# GB202-CC-from-SF-Base.net
KiCad netlist of a schematic drawn in EAGLE
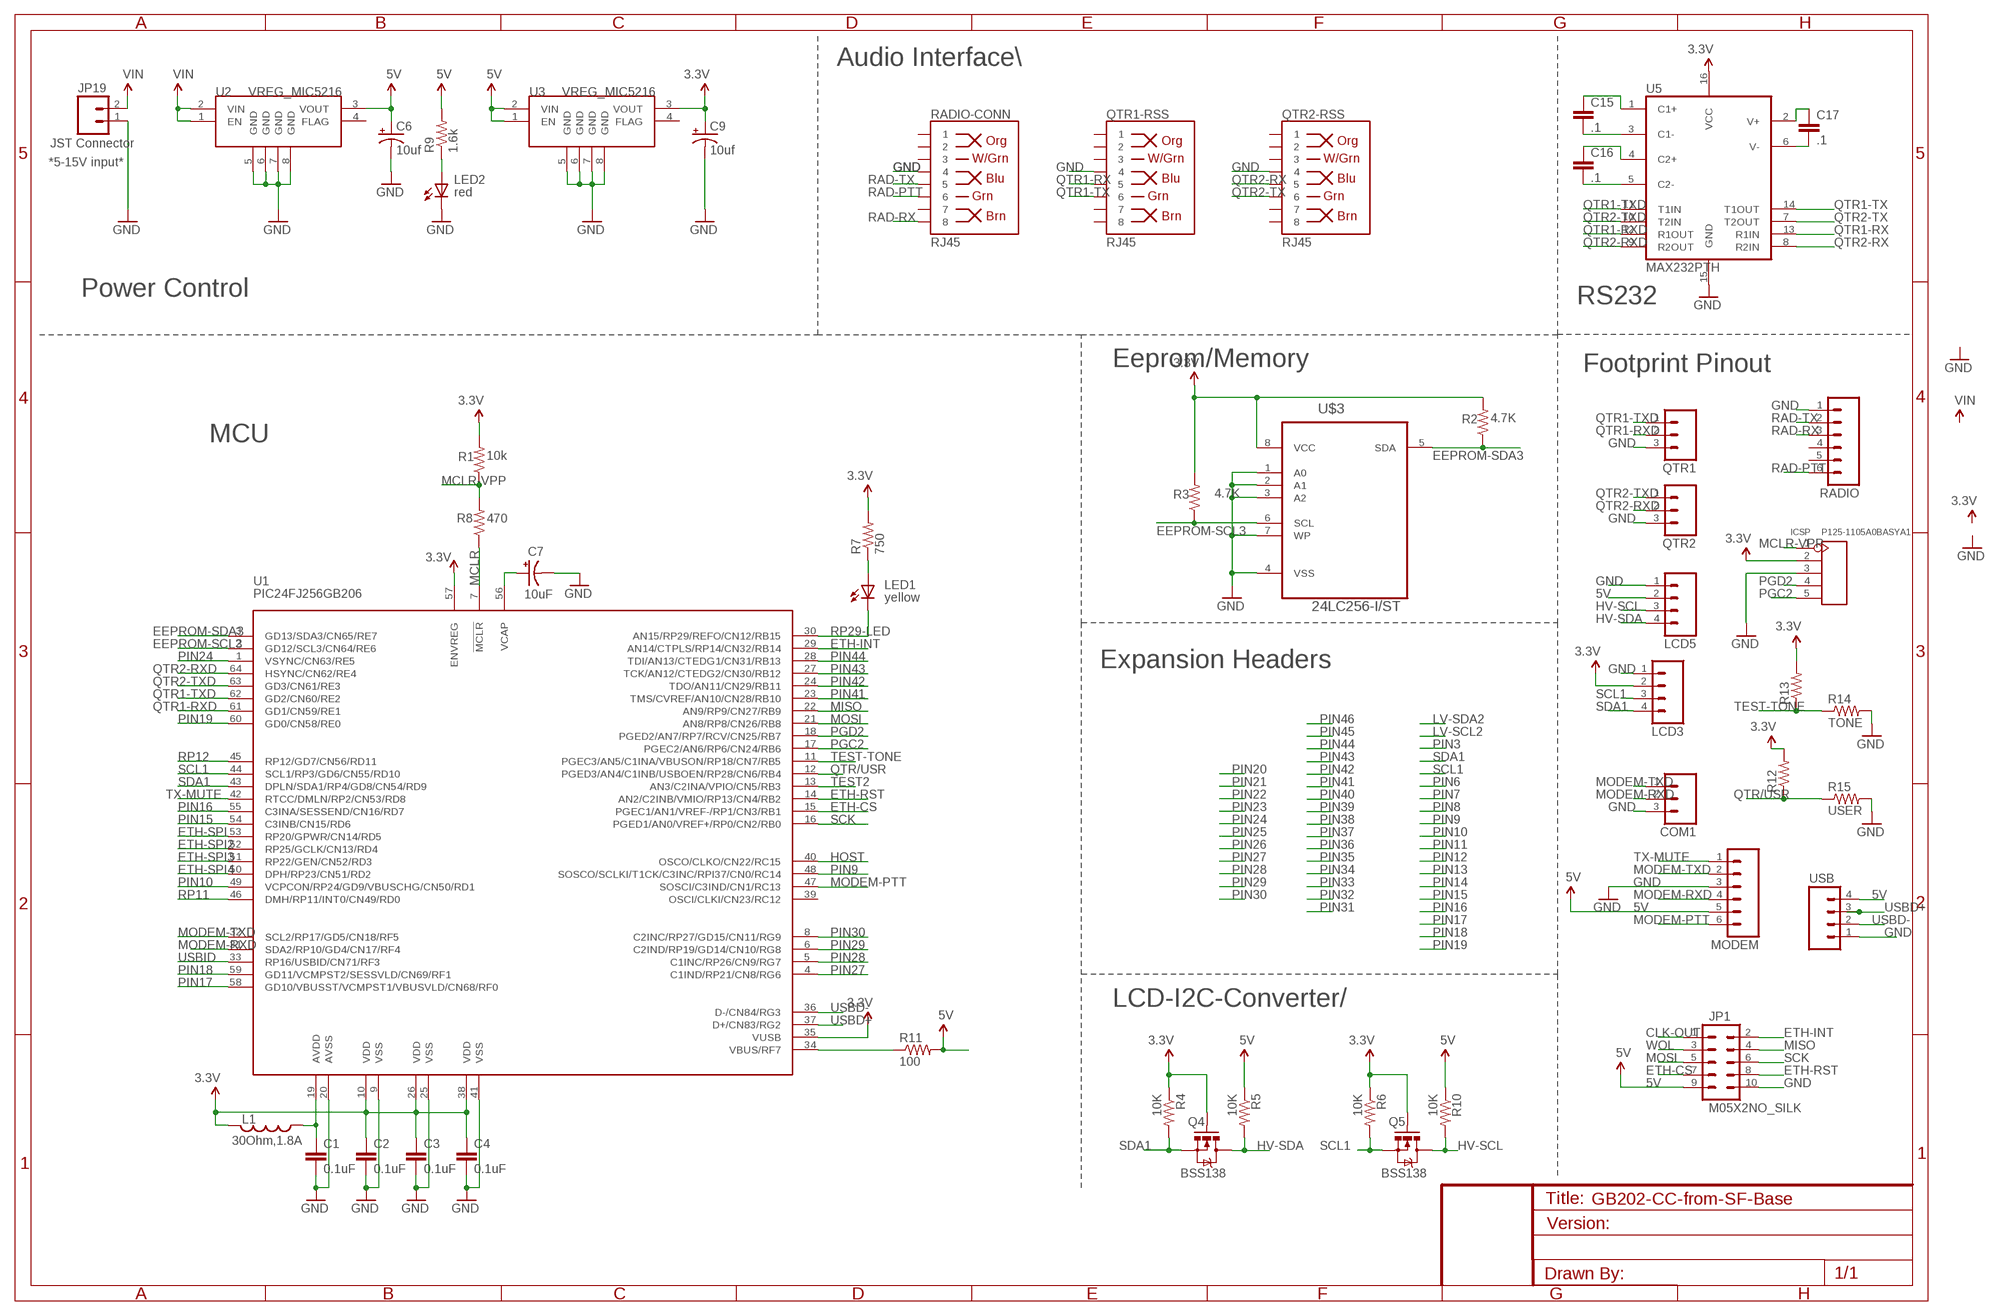
[diagram p0: schematic, sheet 1]

(export (version "E")
  (design (tool "Eeschema 10.0.6"))
  (components
    (comp (ref "C1")
      (value "0.1uF")
      (footprint "eagle-import:0402-CAP")
      (libsource (lib "eagle-import") (part "CAP0402-CAP"))
    )
    (comp (ref "C2")
      (value "0.1uF")
      (footprint "eagle-import:0402-CAP")
      (libsource (lib "eagle-import") (part "CAP0402-CAP"))
    )
    (comp (ref "C3")
      (value "0.1uF")
      (footprint "eagle-import:0402-CAP")
      (libsource (lib "eagle-import") (part "CAP0402-CAP"))
    )
    (comp (ref "C4")
      (value "0.1uF")
      (footprint "eagle-import:0402-CAP")
      (libsource (lib "eagle-import") (part "CAP0402-CAP"))
    )
    (comp (ref "C6")
      (value "10uf")
      (footprint "eagle-import:EIA3216")
      (libsource (lib "eagle-import") (part "SparkFun-Capacitors_CAP_POL1206"))
    )
    (comp (ref "C7")
      (value "10uF")
      (footprint "eagle-import:EIA3216")
      (libsource (lib "eagle-import") (part "CAP_POL1206"))
    )
    (comp (ref "C9")
      (value "10uf")
      (footprint "eagle-import:EIA3216")
      (libsource (lib "eagle-import") (part "SparkFun-Capacitors_CAP_POL1206"))
    )
    (comp (ref "C15")
      (value ".1")
      (footprint "eagle-import:CAP-PTH-SMALL")
      (libsource (lib "eagle-import") (part "CAPPTH"))
    )
    (comp (ref "C16")
      (value ".1")
      (footprint "eagle-import:CAP-PTH-SMALL")
      (libsource (lib "eagle-import") (part "CAPPTH"))
    )
    (comp (ref "C17")
      (value ".1")
      (footprint "eagle-import:CAP-PTH-SMALL")
      (libsource (lib "eagle-import") (part "CAPPTH"))
    )
    (comp (ref "COM1")
      (value "M031X03_NO_SILK")
      (footprint "eagle-import:1X03_NO_SILK")
      (libsource (lib "eagle-import") (part "M031X03_NO_SILK"))
    )
    (comp (ref "ICSP")
      (value "P125-1105A0BASYA1")
      (footprint "eagle-import:H5-2.54")
      (libsource (lib "eagle-import") (part "DIP-BLACK-MALE-HEADER(5P-2.54)"))
    )
    (comp (ref "JP1")
      (value "M05X2NO_SILK")
      (footprint "eagle-import:2X5_NOSILK")
      (libsource (lib "eagle-import") (part "M05X2NO_SILK"))
    )
    (comp (ref "JP19")
      (value "JST Connector")
      (footprint "eagle-import:JST-2-SMD")
      (libsource (lib "eagle-import") (part "M02-JST-2MM-SMT"))
    )
    (comp (ref "L1")
      (value "30Ohm,1.8A")
      (footprint "eagle-import:0603")
      (libsource (lib "eagle-import") (part "INDUCTOR0603"))
    )
    (comp (ref "LCD3")
      (value "M04LONGPADS")
      (footprint "eagle-import:1X04_LONGPADS")
      (libsource (lib "eagle-import") (part "M04LONGPADS"))
    )
    (comp (ref "LCD5")
      (value "M04LONGPADS")
      (footprint "eagle-import:1X04_LONGPADS")
      (libsource (lib "eagle-import") (part "M04LONGPADS"))
    )
    (comp (ref "LED1")
      (value "LY L29K-J1K2-26-Z")
      (footprint "eagle-import:LED-0603")
      (libsource (lib "eagle-import") (part "SparkFun-LED_LED0603"))
    )
    (comp (ref "LED2")
      (value "LS L29K-G1J2-1-Z")
      (footprint "eagle-import:LED-0603")
      (libsource (lib "eagle-import") (part "LED0603"))
    )
    (comp (ref "MODEM")
      (value "M06LONGPADS")
      (footprint "eagle-import:1X06_LONGPADS")
      (libsource (lib "eagle-import") (part "M06LONGPADS"))
    )
    (comp (ref "Q4")
      (value "BSS138")
      (footprint "eagle-import:SOT23-3")
      (libsource (lib "eagle-import") (part "MOSFET-NCHANNELSMD"))
    )
    (comp (ref "Q5")
      (value "BSS138")
      (footprint "eagle-import:SOT23-3")
      (libsource (lib "eagle-import") (part "MOSFET-NCHANNELSMD"))
    )
    (comp (ref "QTR1")
      (value "M031X03_NO_SILK")
      (footprint "eagle-import:1X03_NO_SILK")
      (libsource (lib "eagle-import") (part "M031X03_NO_SILK"))
    )
    (comp (ref "QTR1-RSS")
      (value "RJ45")
      (footprint "eagle-import:RJ45-8")
      (libsource (lib "eagle-import") (part "RJ45-8PTH"))
    )
    (comp (ref "QTR2")
      (value "M031X03_NO_SILK")
      (footprint "eagle-import:1X03_NO_SILK")
      (libsource (lib "eagle-import") (part "M031X03_NO_SILK"))
    )
    (comp (ref "QTR2-RSS")
      (value "RJ45")
      (footprint "eagle-import:RJ45-8")
      (libsource (lib "eagle-import") (part "RJ45-8PTH"))
    )
    (comp (ref "R1")
      (value "10k")
      (footprint "eagle-import:R0402")
      (libsource (lib "eagle-import") (part "R-US_R0402"))
    )
    (comp (ref "R2")
      (value "4.7K")
      (footprint "eagle-import:R0402")
      (libsource (lib "eagle-import") (part "R-US_R0402"))
    )
    (comp (ref "R3")
      (value "4.7K")
      (footprint "eagle-import:R0402")
      (libsource (lib "eagle-import") (part "R-US_R0402"))
    )
    (comp (ref "R4")
      (value "10K")
      (footprint "eagle-import:0402-RES")
      (libsource (lib "eagle-import") (part "RESISTOR0402-RES"))
    )
    (comp (ref "R5")
      (value "10K")
      (footprint "eagle-import:0603-RES")
      (libsource (lib "eagle-import") (part "RESISTOR0603-RES"))
    )
    (comp (ref "R6")
      (value "10K")
      (footprint "eagle-import:0402-RES")
      (libsource (lib "eagle-import") (part "RESISTOR0402-RES"))
    )
    (comp (ref "R7")
      (value "750")
      (footprint "eagle-import:0603-RES")
      (libsource (lib "eagle-import") (part "SparkFun-Resistors_RESISTOR0603-RES"))
    )
    (comp (ref "R8")
      (value "470")
      (footprint "eagle-import:R0402")
      (libsource (lib "eagle-import") (part "R-US_R0402"))
    )
    (comp (ref "R9")
      (value "1.6k")
      (footprint "eagle-import:0603-RES")
      (libsource (lib "eagle-import") (part "SparkFun-Resistors_RESISTOR0603-RES"))
    )
    (comp (ref "R10")
      (value "10K")
      (footprint "eagle-import:0603-RES")
      (libsource (lib "eagle-import") (part "RESISTOR0603-RES"))
    )
    (comp (ref "R11")
      (value "100")
      (footprint "eagle-import:0402-RES")
      (libsource (lib "eagle-import") (part "RESISTOR0402-RES"))
    )
    (comp (ref "R12")
      (value "R-US_R0402")
      (footprint "eagle-import:R0402")
      (libsource (lib "eagle-import") (part "R-US_R0402"))
    )
    (comp (ref "R13")
      (value "R-US_R0402")
      (footprint "eagle-import:R0402")
      (libsource (lib "eagle-import") (part "R-US_R0402"))
    )
    (comp (ref "R14")
      (value "TONE")
      (footprint "eagle-import:R1206")
      (libsource (lib "eagle-import") (part "R-US_R1206"))
    )
    (comp (ref "R15")
      (value "USER")
      (footprint "eagle-import:R1206")
      (libsource (lib "eagle-import") (part "R-US_R1206"))
    )
    (comp (ref "RADIO")
      (value "M06LONGPADS")
      (footprint "eagle-import:1X06_LONGPADS")
      (libsource (lib "eagle-import") (part "M06LONGPADS"))
    )
    (comp (ref "RADIO-CONN")
      (value "RJ45")
      (footprint "eagle-import:RJ45-8")
      (libsource (lib "eagle-import") (part "RJ45-8PTH"))
    )
    (comp (ref "U$3")
      (value "24LC256-I/ST")
      (footprint "eagle-import:SOP65P638X110-8N")
      (libsource (lib "eagle-import") (part "24LC256-I/ST"))
    )
    (comp (ref "U1")
      (value "PIC24FJ256GB206")
      (footprint "eagle-import:PIC24FXXX_TQFP64")
      (libsource (lib "eagle-import") (part "PIC24FXXXDAX06"))
    )
    (comp (ref "U2")
      (value "VREG_MIC5216")
      (footprint "eagle-import:MSOP8")
      (libsource (lib "eagle-import") (part "VREG_MIC5216"))
    )
    (comp (ref "U3")
      (value "VREG_MIC5216")
      (footprint "eagle-import:MSOP8")
      (libsource (lib "eagle-import") (part "VREG_MIC5216"))
    )
    (comp (ref "U5")
      (value "MAX232PTH")
      (footprint "eagle-import:DIL16")
      (libsource (lib "eagle-import") (part "MAX232PTH"))
    )
    (comp (ref "USB")
      (value "M04PTH")
      (footprint "eagle-import:1X04")
      (libsource (lib "eagle-import") (part "M04PTH"))
    )
  )
  (nets
    (net (code "1") (name "/CLK-OUT") (class "Default")
      (node (ref "JP1") (pin "1") (pinfunction "1_1") (pintype "passive"))
    )
    (net (code "2") (name "/EEPROM-SCL3") (class "Default")
      (node (ref "R3") (pin "1") (pinfunction "1_1") (pintype "passive"))
      (node (ref "U$3") (pin "6") (pinfunction "SCL_6") (pintype "input"))
      (node (ref "U1") (pin "2") (pinfunction "GD12/SCL3/CN64/RE6_2") (pintype "bidirectional"))
    )
    (net (code "3") (name "/EEPROM-SDA3") (class "Default")
      (node (ref "R2") (pin "1") (pinfunction "1_1") (pintype "passive"))
      (node (ref "U$3") (pin "5") (pinfunction "SDA_5") (pintype "bidirectional"))
      (node (ref "U1") (pin "3") (pinfunction "GD13/SDA3/CN65/RE7_3") (pintype "bidirectional"))
    )
    (net (code "4") (name "/ETH-CS") (class "Default")
      (node (ref "JP1") (pin "7") (pinfunction "7_7") (pintype "passive"))
      (node (ref "U1") (pin "15") (pinfunction "PGEC1/AN1/VREF-/RP1/CN3/RB1_15") (pintype "bidirectional"))
    )
    (net (code "5") (name "/ETH-INT") (class "Default")
      (node (ref "JP1") (pin "2") (pinfunction "2_2") (pintype "passive"))
      (node (ref "U1") (pin "29") (pinfunction "AN14/CTPLS/RP14/CN32/RB14_29") (pintype "bidirectional"))
    )
    (net (code "6") (name "/ETH-RST") (class "Default")
      (node (ref "JP1") (pin "8") (pinfunction "8_8") (pintype "passive"))
      (node (ref "U1") (pin "14") (pinfunction "AN2/C2INB/VMIO/RP13/CN4/RB2_14") (pintype "bidirectional"))
    )
    (net (code "7") (name "/ETH-SPI") (class "Default")
      (node (ref "U1") (pin "53") (pinfunction "RP20/GPWR/CN14/RD5_53") (pintype "bidirectional"))
    )
    (net (code "8") (name "/ETH-SPI2") (class "Default")
      (node (ref "U1") (pin "52") (pinfunction "RP25/GCLK/CN13/RD4_52") (pintype "bidirectional"))
    )
    (net (code "9") (name "/ETH-SPI3") (class "Default")
      (node (ref "U1") (pin "51") (pinfunction "RP22/GEN/CN52/RD3_51") (pintype "bidirectional"))
    )
    (net (code "10") (name "/ETH-SPI4") (class "Default")
      (node (ref "U1") (pin "50") (pinfunction "DPH/RP23/CN51/RD2_50") (pintype "bidirectional"))
    )
    (net (code "11") (name "/HOST") (class "Default")
      (node (ref "U1") (pin "40") (pinfunction "OSCO/CLKO/CN22/RC15_40") (pintype "bidirectional"))
    )
    (net (code "12") (name "/HV-SCL") (class "Default")
      (node (ref "LCD5") (pin "3") (pinfunction "3_3") (pintype "passive"))
      (node (ref "Q5") (pin "3") (pinfunction "D_3") (pintype "passive"))
      (node (ref "R10") (pin "2") (pinfunction "2_2") (pintype "passive"))
    )
    (net (code "13") (name "/HV-SDA") (class "Default")
      (node (ref "LCD5") (pin "4") (pinfunction "4_4") (pintype "passive"))
      (node (ref "Q4") (pin "3") (pinfunction "D_3") (pintype "passive"))
      (node (ref "R5") (pin "2") (pinfunction "2_2") (pintype "passive"))
    )
    (net (code "16") (name "/MCLR") (class "Default")
      (node (ref "R8") (pin "1") (pinfunction "1_1") (pintype "passive"))
      (node (ref "U1") (pin "7") (pinfunction "~{MCLR}_7") (pintype "input"))
    )
    (net (code "17") (name "/MCLR-VPP") (class "Default")
      (node (ref "ICSP") (pin "1") (pinfunction "1_1") (pintype "bidirectional"))
      (node (ref "R1") (pin "1") (pinfunction "1_1") (pintype "passive"))
      (node (ref "R8") (pin "2") (pinfunction "2_2") (pintype "passive"))
    )
    (net (code "18") (name "/MISO") (class "Default")
      (node (ref "JP1") (pin "4") (pinfunction "4_4") (pintype "passive"))
      (node (ref "U1") (pin "22") (pinfunction "AN9/RP9/CN27/RB9_22") (pintype "bidirectional"))
    )
    (net (code "19") (name "/MODEM-PTT") (class "Default")
      (node (ref "MODEM") (pin "6") (pinfunction "6_6") (pintype "passive"))
      (node (ref "U1") (pin "47") (pinfunction "SOSCI/C3IND/CN1/RC13_47") (pintype "bidirectional"))
    )
    (net (code "20") (name "/MODEM-RXD") (class "Default")
      (node (ref "COM1") (pin "2") (pinfunction "2_2") (pintype "passive"))
      (node (ref "MODEM") (pin "4") (pinfunction "4_4") (pintype "passive"))
      (node (ref "U1") (pin "31") (pinfunction "SDA2/RP10/GD4/CN17/RF4_31") (pintype "bidirectional"))
    )
    (net (code "21") (name "/MODEM-TXD") (class "Default")
      (node (ref "COM1") (pin "1") (pinfunction "1_1") (pintype "passive"))
      (node (ref "MODEM") (pin "2") (pinfunction "2_2") (pintype "passive"))
      (node (ref "U1") (pin "32") (pinfunction "SCL2/RP17/GD5/CN18/RF5_32") (pintype "bidirectional"))
    )
    (net (code "22") (name "/MOSI") (class "Default")
      (node (ref "JP1") (pin "5") (pinfunction "5_5") (pintype "passive"))
      (node (ref "U1") (pin "21") (pinfunction "AN8/RP8/CN26/RB8_21") (pintype "bidirectional"))
    )
    (net (code "23") (name "/PGC2") (class "Default")
      (node (ref "ICSP") (pin "5") (pinfunction "5_5") (pintype "bidirectional"))
      (node (ref "U1") (pin "17") (pinfunction "PGEC2/AN6/RP6/CN24/RB6_17") (pintype "bidirectional"))
    )
    (net (code "24") (name "/PGD2") (class "Default")
      (node (ref "ICSP") (pin "4") (pinfunction "4_4") (pintype "bidirectional"))
      (node (ref "U1") (pin "18") (pinfunction "PGED2/AN7/RP7/RCV/CN25/RB7_18") (pintype "bidirectional"))
    )
    (net (code "29") (name "/PIN9") (class "Default")
      (node (ref "U1") (pin "48") (pinfunction "SOSCO/SCLKI/T1CK/C3INC/RPI37/CN0/RC14_48") (pintype "bidirectional"))
    )
    (net (code "30") (name "/PIN10") (class "Default")
      (node (ref "U1") (pin "49") (pinfunction "VCPCON/RP24/GD9/VBUSCHG/CN50/RD1_49") (pintype "bidirectional"))
    )
    (net (code "35") (name "/PIN15") (class "Default")
      (node (ref "U1") (pin "54") (pinfunction "C3INB/CN15/RD6_54") (pintype "bidirectional"))
    )
    (net (code "36") (name "/PIN16") (class "Default")
      (node (ref "U1") (pin "55") (pinfunction "C3INA/SESSEND/CN16/RD7_55") (pintype "bidirectional"))
    )
    (net (code "37") (name "/PIN17") (class "Default")
      (node (ref "U1") (pin "58") (pinfunction "GD10/VBUSST/VCMPST1/VBUSVLD/CN68/RF0_58") (pintype "bidirectional"))
    )
    (net (code "38") (name "/PIN18") (class "Default")
      (node (ref "U1") (pin "59") (pinfunction "GD11/VCMPST2/SESSVLD/CN69/RF1_59") (pintype "bidirectional"))
    )
    (net (code "39") (name "/PIN19") (class "Default")
      (node (ref "U1") (pin "60") (pinfunction "GD0/CN58/RE0_60") (pintype "bidirectional"))
    )
    (net (code "44") (name "/PIN24") (class "Default")
      (node (ref "U1") (pin "1") (pinfunction "VSYNC/CN63/RE5_1") (pintype "bidirectional"))
    )
    (net (code "47") (name "/PIN27") (class "Default")
      (node (ref "U1") (pin "4") (pinfunction "C1IND/RP21/CN8/RG6_4") (pintype "bidirectional"))
    )
    (net (code "48") (name "/PIN28") (class "Default")
      (node (ref "U1") (pin "5") (pinfunction "C1INC/RP26/CN9/RG7_5") (pintype "bidirectional"))
    )
    (net (code "49") (name "/PIN29") (class "Default")
      (node (ref "U1") (pin "6") (pinfunction "C2IND/RP19/GD14/CN10/RG8_6") (pintype "bidirectional"))
    )
    (net (code "50") (name "/PIN30") (class "Default")
      (node (ref "U1") (pin "8") (pinfunction "C2INC/RP27/GD15/CN11/RG9_8") (pintype "bidirectional"))
    )
    (net (code "61") (name "/PIN41") (class "Default")
      (node (ref "U1") (pin "23") (pinfunction "TMS/CVREF/AN10/CN28/RB10_23") (pintype "bidirectional"))
    )
    (net (code "62") (name "/PIN42") (class "Default")
      (node (ref "U1") (pin "24") (pinfunction "TDO/AN11/CN29/RB11_24") (pintype "bidirectional"))
    )
    (net (code "63") (name "/PIN43") (class "Default")
      (node (ref "U1") (pin "27") (pinfunction "TCK/AN12/CTEDG2/CN30/RB12_27") (pintype "bidirectional"))
    )
    (net (code "64") (name "/PIN44") (class "Default")
      (node (ref "U1") (pin "28") (pinfunction "TDI/AN13/CTEDG1/CN31/RB13_28") (pintype "bidirectional"))
    )
    (net (code "67") (name "/QTR1-RX") (class "Default")
      (node (ref "QTR1-RSS") (pin "5") (pinfunction "5_5") (pintype "bidirectional"))
      (node (ref "U5") (pin "13") (pinfunction "R1IN_13") (pintype "input"))
    )
    (net (code "68") (name "/QTR1-RXD") (class "Default")
      (node (ref "QTR1") (pin "2") (pinfunction "2_2") (pintype "passive"))
      (node (ref "U1") (pin "61") (pinfunction "GD1/CN59/RE1_61") (pintype "bidirectional"))
      (node (ref "U5") (pin "12") (pinfunction "R1OUT_12") (pintype "output"))
    )
    (net (code "69") (name "/QTR1-TX") (class "Default")
      (node (ref "QTR1-RSS") (pin "6") (pinfunction "6_6") (pintype "bidirectional"))
      (node (ref "U5") (pin "14") (pinfunction "T1OUT_14") (pintype "output"))
    )
    (net (code "70") (name "/QTR1-TXD") (class "Default")
      (node (ref "QTR1") (pin "1") (pinfunction "1_1") (pintype "passive"))
      (node (ref "U1") (pin "62") (pinfunction "GD2/CN60/RE2_62") (pintype "bidirectional"))
      (node (ref "U5") (pin "11") (pinfunction "T1IN_11") (pintype "input"))
    )
    (net (code "71") (name "/QTR2-RX") (class "Default")
      (node (ref "QTR2-RSS") (pin "5") (pinfunction "5_5") (pintype "bidirectional"))
      (node (ref "U5") (pin "8") (pinfunction "R2IN_8") (pintype "input"))
    )
    (net (code "72") (name "/QTR2-RXD") (class "Default")
      (node (ref "QTR2") (pin "2") (pinfunction "2_2") (pintype "passive"))
      (node (ref "U1") (pin "64") (pinfunction "HSYNC/CN62/RE4_64") (pintype "bidirectional"))
      (node (ref "U5") (pin "9") (pinfunction "R2OUT_9") (pintype "output"))
    )
    (net (code "73") (name "/QTR2-TX") (class "Default")
      (node (ref "QTR2-RSS") (pin "6") (pinfunction "6_6") (pintype "bidirectional"))
      (node (ref "U5") (pin "7") (pinfunction "T2OUT_7") (pintype "output"))
    )
    (net (code "74") (name "/QTR2-TXD") (class "Default")
      (node (ref "QTR2") (pin "1") (pinfunction "1_1") (pintype "passive"))
      (node (ref "U1") (pin "63") (pinfunction "GD3/CN61/RE3_63") (pintype "bidirectional"))
      (node (ref "U5") (pin "10") (pinfunction "T2IN_10") (pintype "input"))
    )
    (net (code "75") (name "/QTR{slash}USR") (class "Default")
      (node (ref "R12") (pin "1") (pinfunction "1_1") (pintype "passive"))
      (node (ref "R15") (pin "1") (pinfunction "1_1") (pintype "passive"))
      (node (ref "U1") (pin "12") (pinfunction "PGED3/AN4/C1INB/USBOEN/RP28/CN6/RB4_12") (pintype "bidirectional"))
    )
    (net (code "76") (name "/RAD-PTT") (class "Default")
      (node (ref "RADIO") (pin "6") (pinfunction "6_6") (pintype "passive"))
      (node (ref "RADIO-CONN") (pin "6") (pinfunction "6_6") (pintype "bidirectional"))
    )
    (net (code "77") (name "/RAD-RX") (class "Default")
      (node (ref "RADIO") (pin "3") (pinfunction "3_3") (pintype "passive"))
      (node (ref "RADIO-CONN") (pin "8") (pinfunction "8_8") (pintype "bidirectional"))
    )
    (net (code "78") (name "/RAD-TX") (class "Default")
      (node (ref "RADIO") (pin "2") (pinfunction "2_2") (pintype "passive"))
      (node (ref "RADIO-CONN") (pin "5") (pinfunction "5_5") (pintype "bidirectional"))
    )
    (net (code "79") (name "/RP11") (class "Default")
      (node (ref "U1") (pin "46") (pinfunction "DMH/RP11/INT0/CN49/RD0_46") (pintype "bidirectional"))
    )
    (net (code "80") (name "/RP12") (class "Default")
      (node (ref "U1") (pin "45") (pinfunction "RP12/GD7/CN56/RD11_45") (pintype "bidirectional"))
    )
    (net (code "81") (name "/RP29-LED") (class "Default")
      (node (ref "LED1") (pin "C") (pinfunction "C_C") (pintype "passive"))
      (node (ref "U1") (pin "30") (pinfunction "AN15/RP29/REFO/CN12/RB15_30") (pintype "bidirectional"))
    )
    (net (code "82") (name "/SCK") (class "Default")
      (node (ref "JP1") (pin "6") (pinfunction "6_6") (pintype "passive"))
      (node (ref "U1") (pin "16") (pinfunction "PGED1/AN0/VREF+/RP0/CN2/RB0_16") (pintype "bidirectional"))
    )
    (net (code "83") (name "/SCL1") (class "Default")
      (node (ref "LCD3") (pin "3") (pinfunction "3_3") (pintype "passive"))
      (node (ref "Q5") (pin "2") (pinfunction "S_2") (pintype "passive"))
      (node (ref "R6") (pin "2") (pinfunction "2_2") (pintype "passive"))
      (node (ref "U1") (pin "44") (pinfunction "SCL1/RP3/GD6/CN55/RD10_44") (pintype "bidirectional"))
    )
    (net (code "84") (name "/SDA1") (class "Default")
      (node (ref "LCD3") (pin "4") (pinfunction "4_4") (pintype "passive"))
      (node (ref "Q4") (pin "2") (pinfunction "S_2") (pintype "passive"))
      (node (ref "R4") (pin "2") (pinfunction "2_2") (pintype "passive"))
      (node (ref "U1") (pin "43") (pinfunction "DPLN/SDA1/RP4/GD8/CN54/RD9_43") (pintype "bidirectional"))
    )
    (net (code "85") (name "/TEST-TONE") (class "Default")
      (node (ref "R13") (pin "1") (pinfunction "1_1") (pintype "passive"))
      (node (ref "R14") (pin "1") (pinfunction "1_1") (pintype "passive"))
      (node (ref "U1") (pin "11") (pinfunction "PGEC3/AN5/C1INA/VBUSON/RP18/CN7/RB5_11") (pintype "bidirectional"))
    )
    (net (code "86") (name "/TEST2") (class "Default")
      (node (ref "U1") (pin "13") (pinfunction "AN3/C2INA/VPIO/CN5/RB3_13") (pintype "bidirectional"))
    )
    (net (code "87") (name "/TX-MUTE") (class "Default")
      (node (ref "MODEM") (pin "1") (pinfunction "1_1") (pintype "passive"))
      (node (ref "U1") (pin "42") (pinfunction "RTCC/DMLN/RP2/CN53/RD8_42") (pintype "bidirectional"))
    )
    (net (code "88") (name "/USBD+") (class "Default")
      (node (ref "U1") (pin "37") (pinfunction "D+/CN83/RG2_37") (pintype "bidirectional"))
      (node (ref "USB") (pin "3") (pinfunction "3_3") (pintype "passive"))
    )
    (net (code "89") (name "/USBD-") (class "Default")
      (node (ref "U1") (pin "36") (pinfunction "D-/CN84/RG3_36") (pintype "bidirectional"))
      (node (ref "USB") (pin "2") (pinfunction "2_2") (pintype "passive"))
    )
    (net (code "90") (name "/USBID") (class "Default")
      (node (ref "U1") (pin "33") (pinfunction "RP16/USBID/CN71/RF3_33") (pintype "bidirectional"))
    )
    (net (code "91") (name "/WOL") (class "Default")
      (node (ref "JP1") (pin "3") (pinfunction "3_3") (pintype "passive"))
    )
    (net (code "92") (name "3.3V") (class "Default")
      (node (ref "C2") (pin "1") (pinfunction "1_1") (pintype "passive"))
      (node (ref "C3") (pin "1") (pinfunction "1_1") (pintype "passive"))
      (node (ref "C4") (pin "1") (pinfunction "1_1") (pintype "passive"))
      (node (ref "C9") (pin "A") (pinfunction "+_A") (pintype "passive"))
      (node (ref "ICSP") (pin "2") (pinfunction "2_2") (pintype "bidirectional"))
      (node (ref "L1") (pin "2") (pinfunction "2_2") (pintype "passive"))
      (node (ref "LCD3") (pin "2") (pinfunction "2_2") (pintype "passive"))
      (node (ref "Q4") (pin "1") (pinfunction "G_1") (pintype "passive"))
      (node (ref "Q5") (pin "1") (pinfunction "G_1") (pintype "passive"))
      (node (ref "R1") (pin "2") (pinfunction "2_2") (pintype "passive"))
      (node (ref "R12") (pin "2") (pinfunction "2_2") (pintype "passive"))
      (node (ref "R13") (pin "2") (pinfunction "2_2") (pintype "passive"))
      (node (ref "R2") (pin "2") (pinfunction "2_2") (pintype "passive"))
      (node (ref "R3") (pin "2") (pinfunction "2_2") (pintype "passive"))
      (node (ref "R4") (pin "1") (pinfunction "1_1") (pintype "passive"))
      (node (ref "R6") (pin "1") (pinfunction "1_1") (pintype "passive"))
      (node (ref "R7") (pin "2") (pinfunction "2_2") (pintype "passive"))
      (node (ref "U$3") (pin "8") (pinfunction "VCC_8") (pintype "power_in"))
      (node (ref "U1") (pin "10") (pinfunction "VDD_10") (pintype "power_in"))
      (node (ref "U1") (pin "26") (pinfunction "VDD_26") (pintype "power_in"))
      (node (ref "U1") (pin "35") (pinfunction "VUSB_35") (pintype "power_in"))
      (node (ref "U1") (pin "38") (pinfunction "VDD_38") (pintype "power_in"))
      (node (ref "U1") (pin "57") (pinfunction "ENVREG_57") (pintype "input"))
      (node (ref "U3") (pin "3") (pinfunction "VOUT_3") (pintype "bidirectional"))
      (node (ref "U5") (pin "16") (pinfunction "VCC_16") (pintype "bidirectional"))
    )
    (net (code "93") (name "5V") (class "Default")
      (node (ref "C6") (pin "A") (pinfunction "+_A") (pintype "passive"))
      (node (ref "JP1") (pin "9") (pinfunction "9_9") (pintype "passive"))
      (node (ref "LCD5") (pin "2") (pinfunction "2_2") (pintype "passive"))
      (node (ref "MODEM") (pin "5") (pinfunction "5_5") (pintype "passive"))
      (node (ref "R10") (pin "1") (pinfunction "1_1") (pintype "passive"))
      (node (ref "R11") (pin "2") (pinfunction "2_2") (pintype "passive"))
      (node (ref "R5") (pin "1") (pinfunction "1_1") (pintype "passive"))
      (node (ref "R9") (pin "2") (pinfunction "2_2") (pintype "passive"))
      (node (ref "U2") (pin "3") (pinfunction "VOUT_3") (pintype "bidirectional"))
      (node (ref "U3") (pin "1") (pinfunction "EN_1") (pintype "bidirectional"))
      (node (ref "U3") (pin "2") (pinfunction "VIN_2") (pintype "bidirectional"))
      (node (ref "USB") (pin "4") (pinfunction "4_4") (pintype "passive"))
    )
    (net (code "94") (name "GND") (class "Default")
      (node (ref "C1") (pin "2") (pinfunction "2_2") (pintype "passive"))
      (node (ref "C2") (pin "2") (pinfunction "2_2") (pintype "passive"))
      (node (ref "C3") (pin "2") (pinfunction "2_2") (pintype "passive"))
      (node (ref "C4") (pin "2") (pinfunction "2_2") (pintype "passive"))
      (node (ref "C6") (pin "C") (pinfunction "-_C") (pintype "passive"))
      (node (ref "C7") (pin "C") (pinfunction "-_C") (pintype "passive"))
      (node (ref "C9") (pin "C") (pinfunction "-_C") (pintype "passive"))
      (node (ref "COM1") (pin "3") (pinfunction "3_3") (pintype "passive"))
      (node (ref "ICSP") (pin "3") (pinfunction "3_3") (pintype "bidirectional"))
      (node (ref "JP1") (pin "10") (pinfunction "10_10") (pintype "passive"))
      (node (ref "JP19") (pin "1") (pinfunction "1_1") (pintype "passive"))
      (node (ref "LCD3") (pin "1") (pinfunction "1_1") (pintype "passive"))
      (node (ref "LCD5") (pin "1") (pinfunction "1_1") (pintype "passive"))
      (node (ref "LED2") (pin "C") (pinfunction "C_C") (pintype "passive"))
      (node (ref "MODEM") (pin "3") (pinfunction "3_3") (pintype "passive"))
      (node (ref "QTR1") (pin "3") (pinfunction "3_3") (pintype "passive"))
      (node (ref "QTR1-RSS") (pin "4") (pinfunction "4_4") (pintype "bidirectional"))
      (node (ref "QTR2") (pin "3") (pinfunction "3_3") (pintype "passive"))
      (node (ref "QTR2-RSS") (pin "4") (pinfunction "4_4") (pintype "bidirectional"))
      (node (ref "R14") (pin "2") (pinfunction "2_2") (pintype "passive"))
      (node (ref "R15") (pin "2") (pinfunction "2_2") (pintype "passive"))
      (node (ref "RADIO") (pin "1") (pinfunction "1_1") (pintype "passive"))
      (node (ref "RADIO-CONN") (pin "4") (pinfunction "4_4") (pintype "bidirectional"))
      (node (ref "U$3") (pin "1") (pinfunction "A0_1") (pintype "input"))
      (node (ref "U$3") (pin "2") (pinfunction "A1_2") (pintype "input"))
      (node (ref "U$3") (pin "3") (pinfunction "A2_3") (pintype "input"))
      (node (ref "U$3") (pin "4") (pinfunction "VSS_4") (pintype "passive"))
      (node (ref "U$3") (pin "7") (pinfunction "WP_7") (pintype "input"))
      (node (ref "U1") (pin "20") (pinfunction "AVSS_20") (pintype "power_in"))
      (node (ref "U1") (pin "25") (pinfunction "VSS_25") (pintype "power_in"))
      (node (ref "U1") (pin "41") (pinfunction "VSS_41") (pintype "power_in"))
      (node (ref "U1") (pin "9") (pinfunction "VSS_9") (pintype "power_in"))
      (node (ref "U2") (pin "5") (pinfunction "GND_5") (pintype "bidirectional"))
      (node (ref "U2") (pin "6") (pinfunction "GND_6") (pintype "bidirectional"))
      (node (ref "U2") (pin "7") (pinfunction "GND_7") (pintype "bidirectional"))
      (node (ref "U2") (pin "8") (pinfunction "GND_8") (pintype "bidirectional"))
      (node (ref "U3") (pin "5") (pinfunction "GND_5") (pintype "bidirectional"))
      (node (ref "U3") (pin "6") (pinfunction "GND_6") (pintype "bidirectional"))
      (node (ref "U3") (pin "7") (pinfunction "GND_7") (pintype "bidirectional"))
      (node (ref "U3") (pin "8") (pinfunction "GND_8") (pintype "bidirectional"))
      (node (ref "U5") (pin "15") (pinfunction "GND_15") (pintype "bidirectional"))
      (node (ref "USB") (pin "1") (pinfunction "1_1") (pintype "passive"))
    )
    (net (code "95") (name "Net-(C7-+)") (class "Default")
      (node (ref "C7") (pin "A") (pinfunction "+_A") (pintype "passive"))
      (node (ref "U1") (pin "56") (pinfunction "VCAP_56") (pintype "power_in"))
    )
    (net (code "96") (name "Net-(LED1-PadA)") (class "Default")
      (node (ref "LED1") (pin "A") (pinfunction "A_A") (pintype "passive"))
      (node (ref "R7") (pin "1") (pinfunction "1_1") (pintype "passive"))
    )
    (net (code "97") (name "Net-(LED2-PadA)") (class "Default")
      (node (ref "LED2") (pin "A") (pinfunction "A_A") (pintype "passive"))
      (node (ref "R9") (pin "1") (pinfunction "1_1") (pintype "passive"))
    )
    (net (code "98") (name "Net-(U1-AVDD)") (class "Default")
      (node (ref "C1") (pin "1") (pinfunction "1_1") (pintype "passive"))
      (node (ref "L1") (pin "1") (pinfunction "1_1") (pintype "passive"))
      (node (ref "U1") (pin "19") (pinfunction "AVDD_19") (pintype "power_in"))
    )
    (net (code "99") (name "Net-(U1-VBUS{slash}RF7)") (class "Default")
      (node (ref "R11") (pin "1") (pinfunction "1_1") (pintype "passive"))
      (node (ref "U1") (pin "34") (pinfunction "VBUS/RF7_34") (pintype "input"))
    )
    (net (code "100") (name "Net-(U5-C1+)") (class "Default")
      (node (ref "C15") (pin "1") (pinfunction "1_1") (pintype "passive"))
      (node (ref "U5") (pin "1") (pinfunction "C1+_1") (pintype "bidirectional"))
    )
    (net (code "101") (name "Net-(U5-C1-)") (class "Default")
      (node (ref "C15") (pin "2") (pinfunction "2_2") (pintype "passive"))
      (node (ref "U5") (pin "3") (pinfunction "C1-_3") (pintype "bidirectional"))
    )
    (net (code "102") (name "Net-(U5-C2+)") (class "Default")
      (node (ref "C16") (pin "1") (pinfunction "1_1") (pintype "passive"))
      (node (ref "U5") (pin "4") (pinfunction "C2+_4") (pintype "bidirectional"))
    )
    (net (code "103") (name "Net-(U5-C2-)") (class "Default")
      (node (ref "C16") (pin "2") (pinfunction "2_2") (pintype "passive"))
      (node (ref "U5") (pin "5") (pinfunction "C2-_5") (pintype "bidirectional"))
    )
    (net (code "104") (name "Net-(U5-V+)") (class "Default")
      (node (ref "C17") (pin "1") (pinfunction "1_1") (pintype "passive"))
      (node (ref "U5") (pin "2") (pinfunction "V+_2") (pintype "bidirectional"))
    )
    (net (code "105") (name "Net-(U5-V-)") (class "Default")
      (node (ref "C17") (pin "2") (pinfunction "2_2") (pintype "passive"))
      (node (ref "U5") (pin "6") (pinfunction "V-_6") (pintype "bidirectional"))
    )
    (net (code "106") (name "VIN") (class "Default")
      (node (ref "JP19") (pin "2") (pinfunction "2_2") (pintype "passive"))
      (node (ref "U2") (pin "1") (pinfunction "EN_1") (pintype "bidirectional"))
      (node (ref "U2") (pin "2") (pinfunction "VIN_2") (pintype "bidirectional"))
    )
    (net (code "107") (name "unconnected-(QTR1-RSS-Pad1)") (class "Default")
      (node (ref "QTR1-RSS") (pin "1") (pinfunction "1_1") (pintype "bidirectional"))
    )
    (net (code "108") (name "unconnected-(QTR1-RSS-Pad2)") (class "Default")
      (node (ref "QTR1-RSS") (pin "2") (pinfunction "2_2") (pintype "bidirectional"))
    )
    (net (code "109") (name "unconnected-(QTR1-RSS-Pad3)") (class "Default")
      (node (ref "QTR1-RSS") (pin "3") (pinfunction "3_3") (pintype "bidirectional"))
    )
    (net (code "110") (name "unconnected-(QTR1-RSS-Pad7)") (class "Default")
      (node (ref "QTR1-RSS") (pin "7") (pinfunction "7_7") (pintype "bidirectional"))
    )
    (net (code "111") (name "unconnected-(QTR1-RSS-Pad8)") (class "Default")
      (node (ref "QTR1-RSS") (pin "8") (pinfunction "8_8") (pintype "bidirectional"))
    )
    (net (code "112") (name "unconnected-(QTR2-RSS-Pad1)") (class "Default")
      (node (ref "QTR2-RSS") (pin "1") (pinfunction "1_1") (pintype "bidirectional"))
    )
    (net (code "113") (name "unconnected-(QTR2-RSS-Pad2)") (class "Default")
      (node (ref "QTR2-RSS") (pin "2") (pinfunction "2_2") (pintype "bidirectional"))
    )
    (net (code "114") (name "unconnected-(QTR2-RSS-Pad3)") (class "Default")
      (node (ref "QTR2-RSS") (pin "3") (pinfunction "3_3") (pintype "bidirectional"))
    )
    (net (code "115") (name "unconnected-(QTR2-RSS-Pad7)") (class "Default")
      (node (ref "QTR2-RSS") (pin "7") (pinfunction "7_7") (pintype "bidirectional"))
    )
    (net (code "116") (name "unconnected-(QTR2-RSS-Pad8)") (class "Default")
      (node (ref "QTR2-RSS") (pin "8") (pinfunction "8_8") (pintype "bidirectional"))
    )
    (net (code "117") (name "unconnected-(RADIO-CONN-Pad1)") (class "Default")
      (node (ref "RADIO-CONN") (pin "1") (pinfunction "1_1") (pintype "bidirectional"))
    )
    (net (code "118") (name "unconnected-(RADIO-CONN-Pad2)") (class "Default")
      (node (ref "RADIO-CONN") (pin "2") (pinfunction "2_2") (pintype "bidirectional"))
    )
    (net (code "119") (name "unconnected-(RADIO-CONN-Pad3)") (class "Default")
      (node (ref "RADIO-CONN") (pin "3") (pinfunction "3_3") (pintype "bidirectional"))
    )
    (net (code "120") (name "unconnected-(RADIO-CONN-Pad7)") (class "Default")
      (node (ref "RADIO-CONN") (pin "7") (pinfunction "7_7") (pintype "bidirectional"))
    )
    (net (code "121") (name "unconnected-(RADIO-Pad4)") (class "Default")
      (node (ref "RADIO") (pin "4") (pinfunction "4_4") (pintype "passive"))
    )
    (net (code "122") (name "unconnected-(RADIO-Pad5)") (class "Default")
      (node (ref "RADIO") (pin "5") (pinfunction "5_5") (pintype "passive"))
    )
    (net (code "123") (name "unconnected-(U1-OSCI{slash}CLKI{slash}CN23{slash}RC12-Pad39)") (class "Default")
      (node (ref "U1") (pin "39") (pinfunction "OSCI/CLKI/CN23/RC12_39") (pintype "bidirectional"))
    )
    (net (code "124") (name "unconnected-(U2-FLAG-Pad4)") (class "Default")
      (node (ref "U2") (pin "4") (pinfunction "FLAG_4") (pintype "bidirectional"))
    )
    (net (code "125") (name "unconnected-(U3-FLAG-Pad4)") (class "Default")
      (node (ref "U3") (pin "4") (pinfunction "FLAG_4") (pintype "bidirectional"))
    )
  )
)
